# FioSaber_Prototype_B.net
KiCad netlist of a schematic drawn in EAGLE
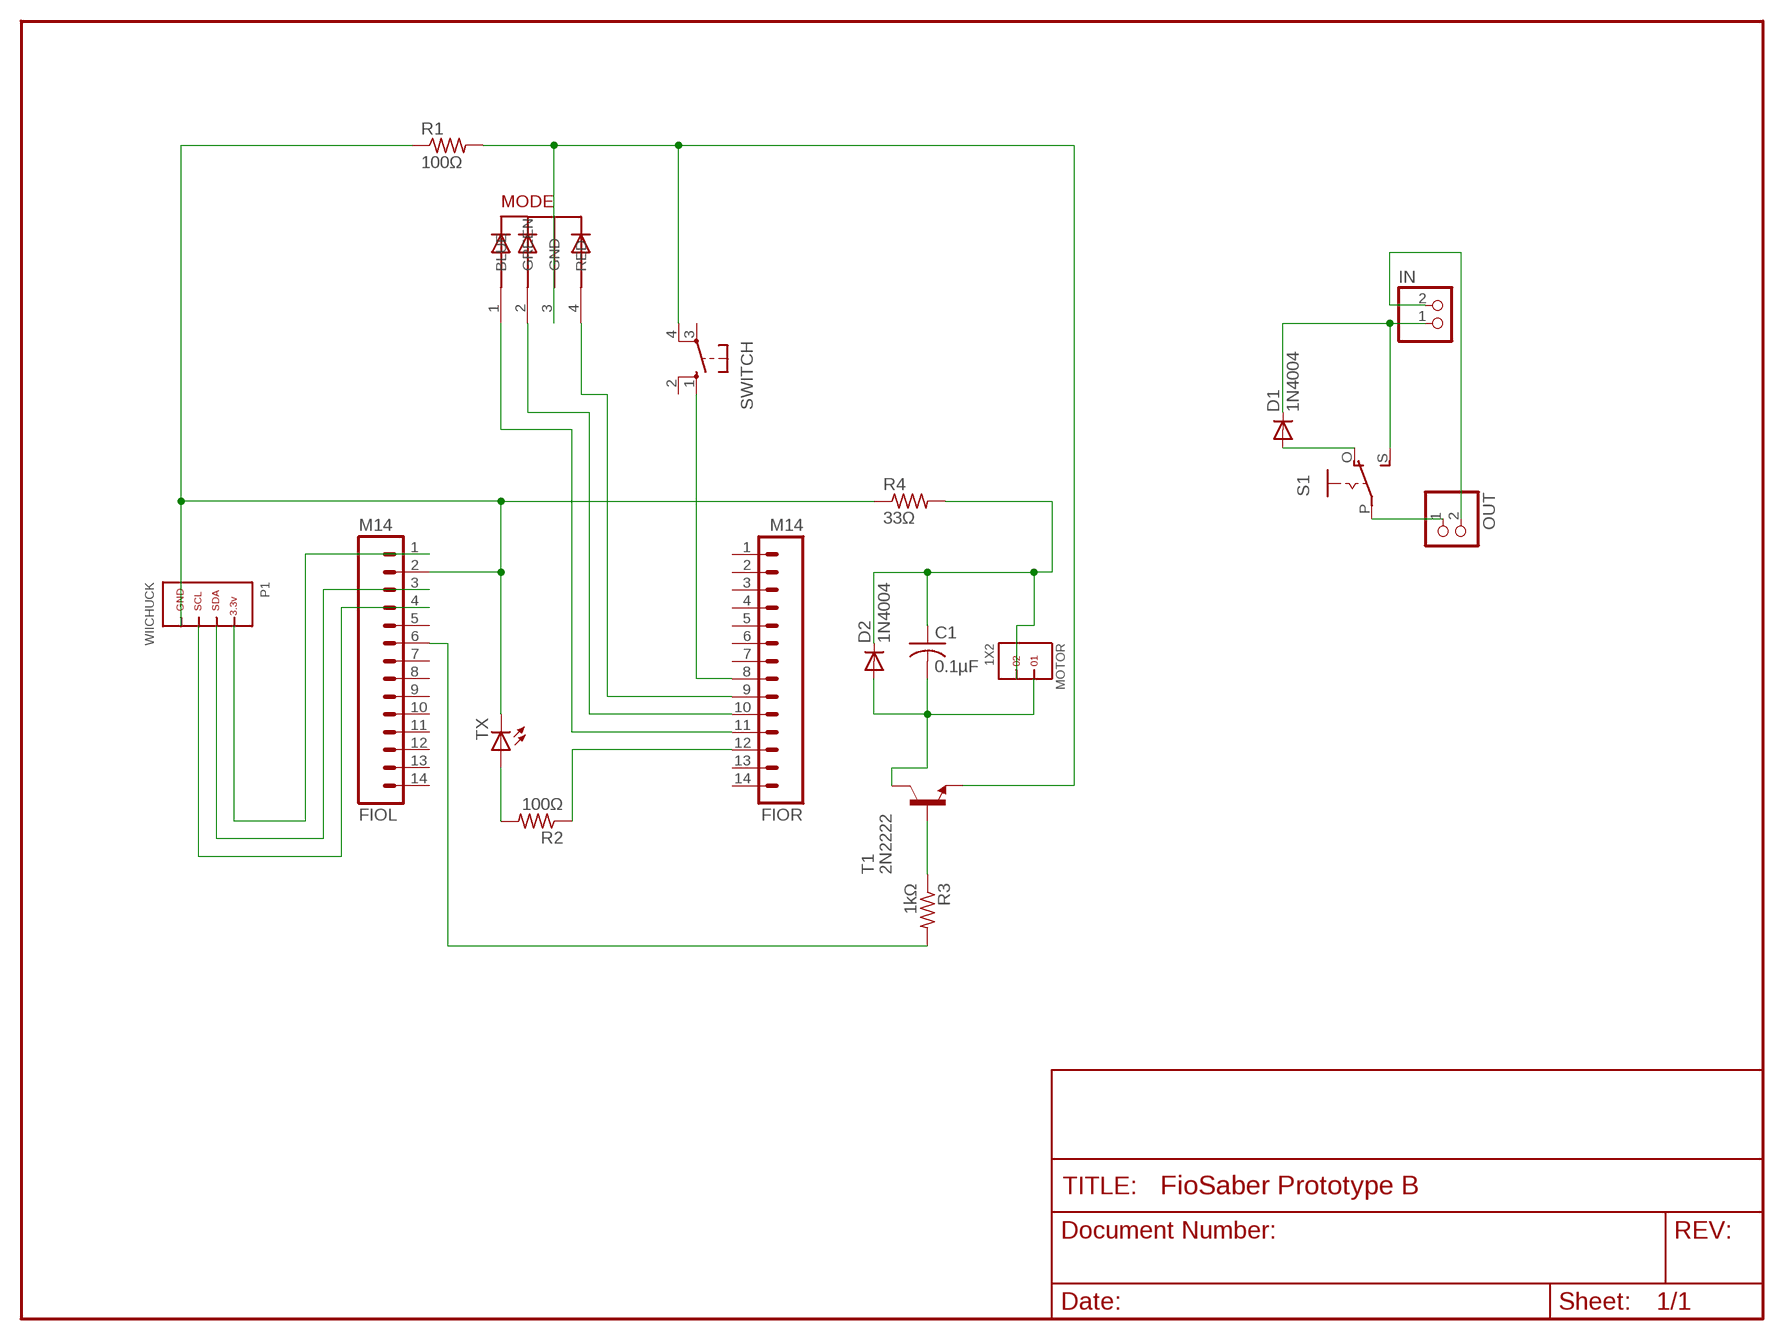
[diagram p0: schematic, sheet 1]

(export (version "E")
  (design (tool "Eeschema 10.0.6"))
  (components
    (comp (ref "C1")
      (value "0.1µF")
      (footprint "eagle-import:C025-025X050")
      (libsource (lib "eagle-import") (part "C-US025-025X050"))
    )
    (comp (ref "D1")
      (value "1N4004")
      (footprint "eagle-import:DO41-10")
      (libsource (lib "eagle-import") (part "1N4004"))
    )
    (comp (ref "D2")
      (value "1N4004")
      (footprint "eagle-import:DO41-10")
      (libsource (lib "eagle-import") (part "1N4004"))
    )
    (comp (ref "FIOL")
      (value "M14")
      (footprint "eagle-import:1X14")
      (libsource (lib "eagle-import") (part "M14"))
    )
    (comp (ref "FIOR")
      (value "M14")
      (footprint "eagle-import:1X14")
      (libsource (lib "eagle-import") (part "M14"))
    )
    (comp (ref "IN")
      (value "JST_2PIN-SMT-RA")
      (footprint "eagle-import:JST-PH-2-SMT-RA")
      (libsource (lib "eagle-import") (part "JST_2PIN-SMT-RA"))
    )
    (comp (ref "MODE")
      (value "5MMRGBLED")
      (footprint "eagle-import:LED5MMRGB")
      (libsource (lib "eagle-import") (part "5MMRGBLED"))
    )
    (comp (ref "MOTOR")
      (value "1X2")
      (footprint "eagle-import:1X2")
      (libsource (lib "eagle-import") (part "1X2"))
    )
    (comp (ref "OUT")
      (value "JST_2PIN-SMT-RA")
      (footprint "eagle-import:JST-PH-2-SMT-RA")
      (libsource (lib "eagle-import") (part "JST_2PIN-SMT-RA"))
    )
    (comp (ref "P1")
      (value "WIICHUCK")
      (footprint "eagle-import:MEMOREX_RECEIVER")
      (libsource (lib "eagle-import") (part "WIICHUCK"))
    )
    (comp (ref "R1")
      (value "100Ω")
      (footprint "eagle-import:0207_7")
      (libsource (lib "eagle-import") (part "R-US_0207/7"))
    )
    (comp (ref "R2")
      (value "100Ω")
      (footprint "eagle-import:0207_7")
      (libsource (lib "eagle-import") (part "R-US_0207/7"))
    )
    (comp (ref "R3")
      (value "1kΩ")
      (footprint "eagle-import:0207_7")
      (libsource (lib "eagle-import") (part "R-US_0207/7"))
    )
    (comp (ref "R4")
      (value "33Ω")
      (footprint "eagle-import:0207_7")
      (libsource (lib "eagle-import") (part "R-US_0207/7"))
    )
    (comp (ref "S1")
      (value "EG1218S")
      (footprint "eagle-import:EG1218")
      (libsource (lib "eagle-import") (part "EG1218S"))
    )
    (comp (ref "SWITCH")
      (value "10-XX")
      (footprint "eagle-import:B3F-10XX")
      (fields (field (name "MPN") "B3F-1000"))
      (libsource (lib "eagle-import") (part "10-XX"))
    )
    (comp (ref "T1")
      (value "2N2222")
      (footprint "eagle-import:TO92-EBC-OVAL")
      (libsource (lib "eagle-import") (part "2N2222"))
    )
    (comp (ref "TX")
      (value "LED3MM")
      (footprint "eagle-import:LED3MM")
      (libsource (lib "eagle-import") (part "LED3MM"))
    )
  )
  (nets
    (net (code "1") (name "Net-(C1-Pad1)") (class "Default")
      (node (ref "C1") (pin "1") (pinfunction "1_1") (pintype "passive"))
      (node (ref "D2") (pin "C") (pinfunction "C_C") (pintype "passive"))
      (node (ref "MOTOR") (pin "2") (pinfunction "2_2") (pintype "bidirectional"))
      (node (ref "R4") (pin "2") (pinfunction "2_2") (pintype "passive"))
    )
    (net (code "2") (name "Net-(C1-Pad2)") (class "Default")
      (node (ref "C1") (pin "2") (pinfunction "2_2") (pintype "passive"))
      (node (ref "D2") (pin "A") (pinfunction "A_A") (pintype "passive"))
      (node (ref "MOTOR") (pin "1") (pinfunction "1_1") (pintype "bidirectional"))
      (node (ref "T1") (pin "C") (pinfunction "C_C") (pintype "passive"))
    )
    (net (code "3") (name "Net-(D1-PadA)") (class "Default")
      (node (ref "D1") (pin "A") (pinfunction "A_A") (pintype "passive"))
      (node (ref "S1") (pin "O") (pinfunction "O_O") (pintype "passive"))
    )
    (net (code "4") (name "Net-(FIOL-Pad1)") (class "Default")
      (node (ref "FIOL") (pin "1") (pinfunction "1_1") (pintype "passive"))
      (node (ref "P1") (pin "PWR") (pinfunction "PWR_PWR") (pintype "bidirectional"))
    )
    (net (code "5") (name "Net-(FIOL-Pad3)") (class "Default")
      (node (ref "FIOL") (pin "3") (pinfunction "3_3") (pintype "passive"))
      (node (ref "P1") (pin "SDA") (pinfunction "SDA_SDA") (pintype "bidirectional"))
    )
    (net (code "6") (name "Net-(FIOL-Pad4)") (class "Default")
      (node (ref "FIOL") (pin "4") (pinfunction "4_4") (pintype "passive"))
      (node (ref "P1") (pin "SCL") (pinfunction "SCL_SCL") (pintype "bidirectional"))
    )
    (net (code "7") (name "Net-(FIOL-Pad6)") (class "Default")
      (node (ref "FIOL") (pin "6") (pinfunction "6_6") (pintype "passive"))
      (node (ref "R3") (pin "2") (pinfunction "2_2") (pintype "passive"))
    )
    (net (code "8") (name "Net-(FIOR-Pad12)") (class "Default")
      (node (ref "FIOR") (pin "12") (pinfunction "12_12") (pintype "passive"))
      (node (ref "R2") (pin "1") (pinfunction "1_1") (pintype "passive"))
    )
    (net (code "9") (name "Net-(IN-1)") (class "Default")
      (node (ref "IN") (pin "2") (pinfunction "1_2") (pintype "passive"))
      (node (ref "OUT") (pin "2") (pinfunction "1_2") (pintype "passive"))
    )
    (net (code "10") (name "Net-(IN-2)") (class "Default")
      (node (ref "D1") (pin "C") (pinfunction "C_C") (pintype "passive"))
      (node (ref "IN") (pin "1") (pinfunction "2_1") (pintype "passive"))
      (node (ref "S1") (pin "S") (pinfunction "S_S") (pintype "passive"))
    )
    (net (code "11") (name "Net-(MODE-BLUE)") (class "Default")
      (node (ref "FIOR") (pin "11") (pinfunction "11_11") (pintype "passive"))
      (node (ref "MODE") (pin "1") (pinfunction "BLUE_1") (pintype "bidirectional"))
    )
    (net (code "12") (name "Net-(MODE-GND)") (class "Default")
      (node (ref "MODE") (pin "3") (pinfunction "GND_3") (pintype "bidirectional"))
      (node (ref "R1") (pin "2") (pinfunction "2_2") (pintype "passive"))
      (node (ref "SWITCH") (pin "4") (pinfunction "P1_4") (pintype "passive"))
      (node (ref "T1") (pin "E") (pinfunction "E_E") (pintype "passive"))
    )
    (net (code "13") (name "Net-(MODE-GREEN)") (class "Default")
      (node (ref "FIOR") (pin "10") (pinfunction "10_10") (pintype "passive"))
      (node (ref "MODE") (pin "2") (pinfunction "GREEN_2") (pintype "bidirectional"))
    )
    (net (code "14") (name "Net-(MODE-RED)") (class "Default")
      (node (ref "FIOR") (pin "9") (pinfunction "9_9") (pintype "passive"))
      (node (ref "MODE") (pin "4") (pinfunction "RED_4") (pintype "bidirectional"))
    )
    (net (code "15") (name "Net-(OUT-2)") (class "Default")
      (node (ref "OUT") (pin "1") (pinfunction "2_1") (pintype "passive"))
      (node (ref "S1") (pin "P") (pinfunction "P_P") (pintype "passive"))
    )
    (net (code "16") (name "Net-(R2-Pad2)") (class "Default")
      (node (ref "R2") (pin "2") (pinfunction "2_2") (pintype "passive"))
      (node (ref "TX") (pin "A") (pinfunction "A_A") (pintype "passive"))
    )
    (net (code "17") (name "Net-(R3-Pad1)") (class "Default")
      (node (ref "R3") (pin "1") (pinfunction "1_1") (pintype "passive"))
      (node (ref "T1") (pin "B") (pinfunction "B_B") (pintype "passive"))
    )
    (net (code "18") (name "Net-(SWITCH-S)") (class "Default")
      (node (ref "FIOR") (pin "8") (pinfunction "8_8") (pintype "passive"))
      (node (ref "SWITCH") (pin "1") (pinfunction "S_1") (pintype "passive"))
    )
    (net (code "19") (name "Net-(TX-C)") (class "Default")
      (node (ref "FIOL") (pin "2") (pinfunction "2_2") (pintype "passive"))
      (node (ref "P1") (pin "GND") (pinfunction "GND_GND") (pintype "bidirectional"))
      (node (ref "R1") (pin "1") (pinfunction "1_1") (pintype "passive"))
      (node (ref "R4") (pin "1") (pinfunction "1_1") (pintype "passive"))
      (node (ref "TX") (pin "K") (pinfunction "C_K") (pintype "passive"))
    )
    (net (code "20") (name "unconnected-(FIOL-Pad5)") (class "Default")
      (node (ref "FIOL") (pin "5") (pinfunction "5_5") (pintype "passive"))
    )
    (net (code "21") (name "unconnected-(FIOL-Pad7)") (class "Default")
      (node (ref "FIOL") (pin "7") (pinfunction "7_7") (pintype "passive"))
    )
    (net (code "22") (name "unconnected-(FIOL-Pad8)") (class "Default")
      (node (ref "FIOL") (pin "8") (pinfunction "8_8") (pintype "passive"))
    )
    (net (code "23") (name "unconnected-(FIOL-Pad9)") (class "Default")
      (node (ref "FIOL") (pin "9") (pinfunction "9_9") (pintype "passive"))
    )
    (net (code "24") (name "unconnected-(FIOL-Pad10)") (class "Default")
      (node (ref "FIOL") (pin "10") (pinfunction "10_10") (pintype "passive"))
    )
    (net (code "25") (name "unconnected-(FIOL-Pad11)") (class "Default")
      (node (ref "FIOL") (pin "11") (pinfunction "11_11") (pintype "passive"))
    )
    (net (code "26") (name "unconnected-(FIOL-Pad12)") (class "Default")
      (node (ref "FIOL") (pin "12") (pinfunction "12_12") (pintype "passive"))
    )
    (net (code "27") (name "unconnected-(FIOL-Pad13)") (class "Default")
      (node (ref "FIOL") (pin "13") (pinfunction "13_13") (pintype "passive"))
    )
    (net (code "28") (name "unconnected-(FIOL-Pad14)") (class "Default")
      (node (ref "FIOL") (pin "14") (pinfunction "14_14") (pintype "passive"))
    )
    (net (code "29") (name "unconnected-(FIOR-Pad1)") (class "Default")
      (node (ref "FIOR") (pin "1") (pinfunction "1_1") (pintype "passive"))
    )
    (net (code "30") (name "unconnected-(FIOR-Pad2)") (class "Default")
      (node (ref "FIOR") (pin "2") (pinfunction "2_2") (pintype "passive"))
    )
    (net (code "31") (name "unconnected-(FIOR-Pad3)") (class "Default")
      (node (ref "FIOR") (pin "3") (pinfunction "3_3") (pintype "passive"))
    )
    (net (code "32") (name "unconnected-(FIOR-Pad4)") (class "Default")
      (node (ref "FIOR") (pin "4") (pinfunction "4_4") (pintype "passive"))
    )
    (net (code "33") (name "unconnected-(FIOR-Pad5)") (class "Default")
      (node (ref "FIOR") (pin "5") (pinfunction "5_5") (pintype "passive"))
    )
    (net (code "34") (name "unconnected-(FIOR-Pad6)") (class "Default")
      (node (ref "FIOR") (pin "6") (pinfunction "6_6") (pintype "passive"))
    )
    (net (code "35") (name "unconnected-(FIOR-Pad7)") (class "Default")
      (node (ref "FIOR") (pin "7") (pinfunction "7_7") (pintype "passive"))
    )
    (net (code "36") (name "unconnected-(FIOR-Pad13)") (class "Default")
      (node (ref "FIOR") (pin "13") (pinfunction "13_13") (pintype "passive"))
    )
    (net (code "37") (name "unconnected-(FIOR-Pad14)") (class "Default")
      (node (ref "FIOR") (pin "14") (pinfunction "14_14") (pintype "passive"))
    )
    (net (code "38") (name "unconnected-(SWITCH-P-Pad3)") (class "Default")
      (node (ref "SWITCH") (pin "3") (pinfunction "P_3") (pintype "passive"))
    )
    (net (code "39") (name "unconnected-(SWITCH-S1-Pad2)") (class "Default")
      (node (ref "SWITCH") (pin "2") (pinfunction "S1_2") (pintype "passive"))
    )
  )
)
